# WBD_02.net
KiCad netlist of a schematic drawn in EAGLE
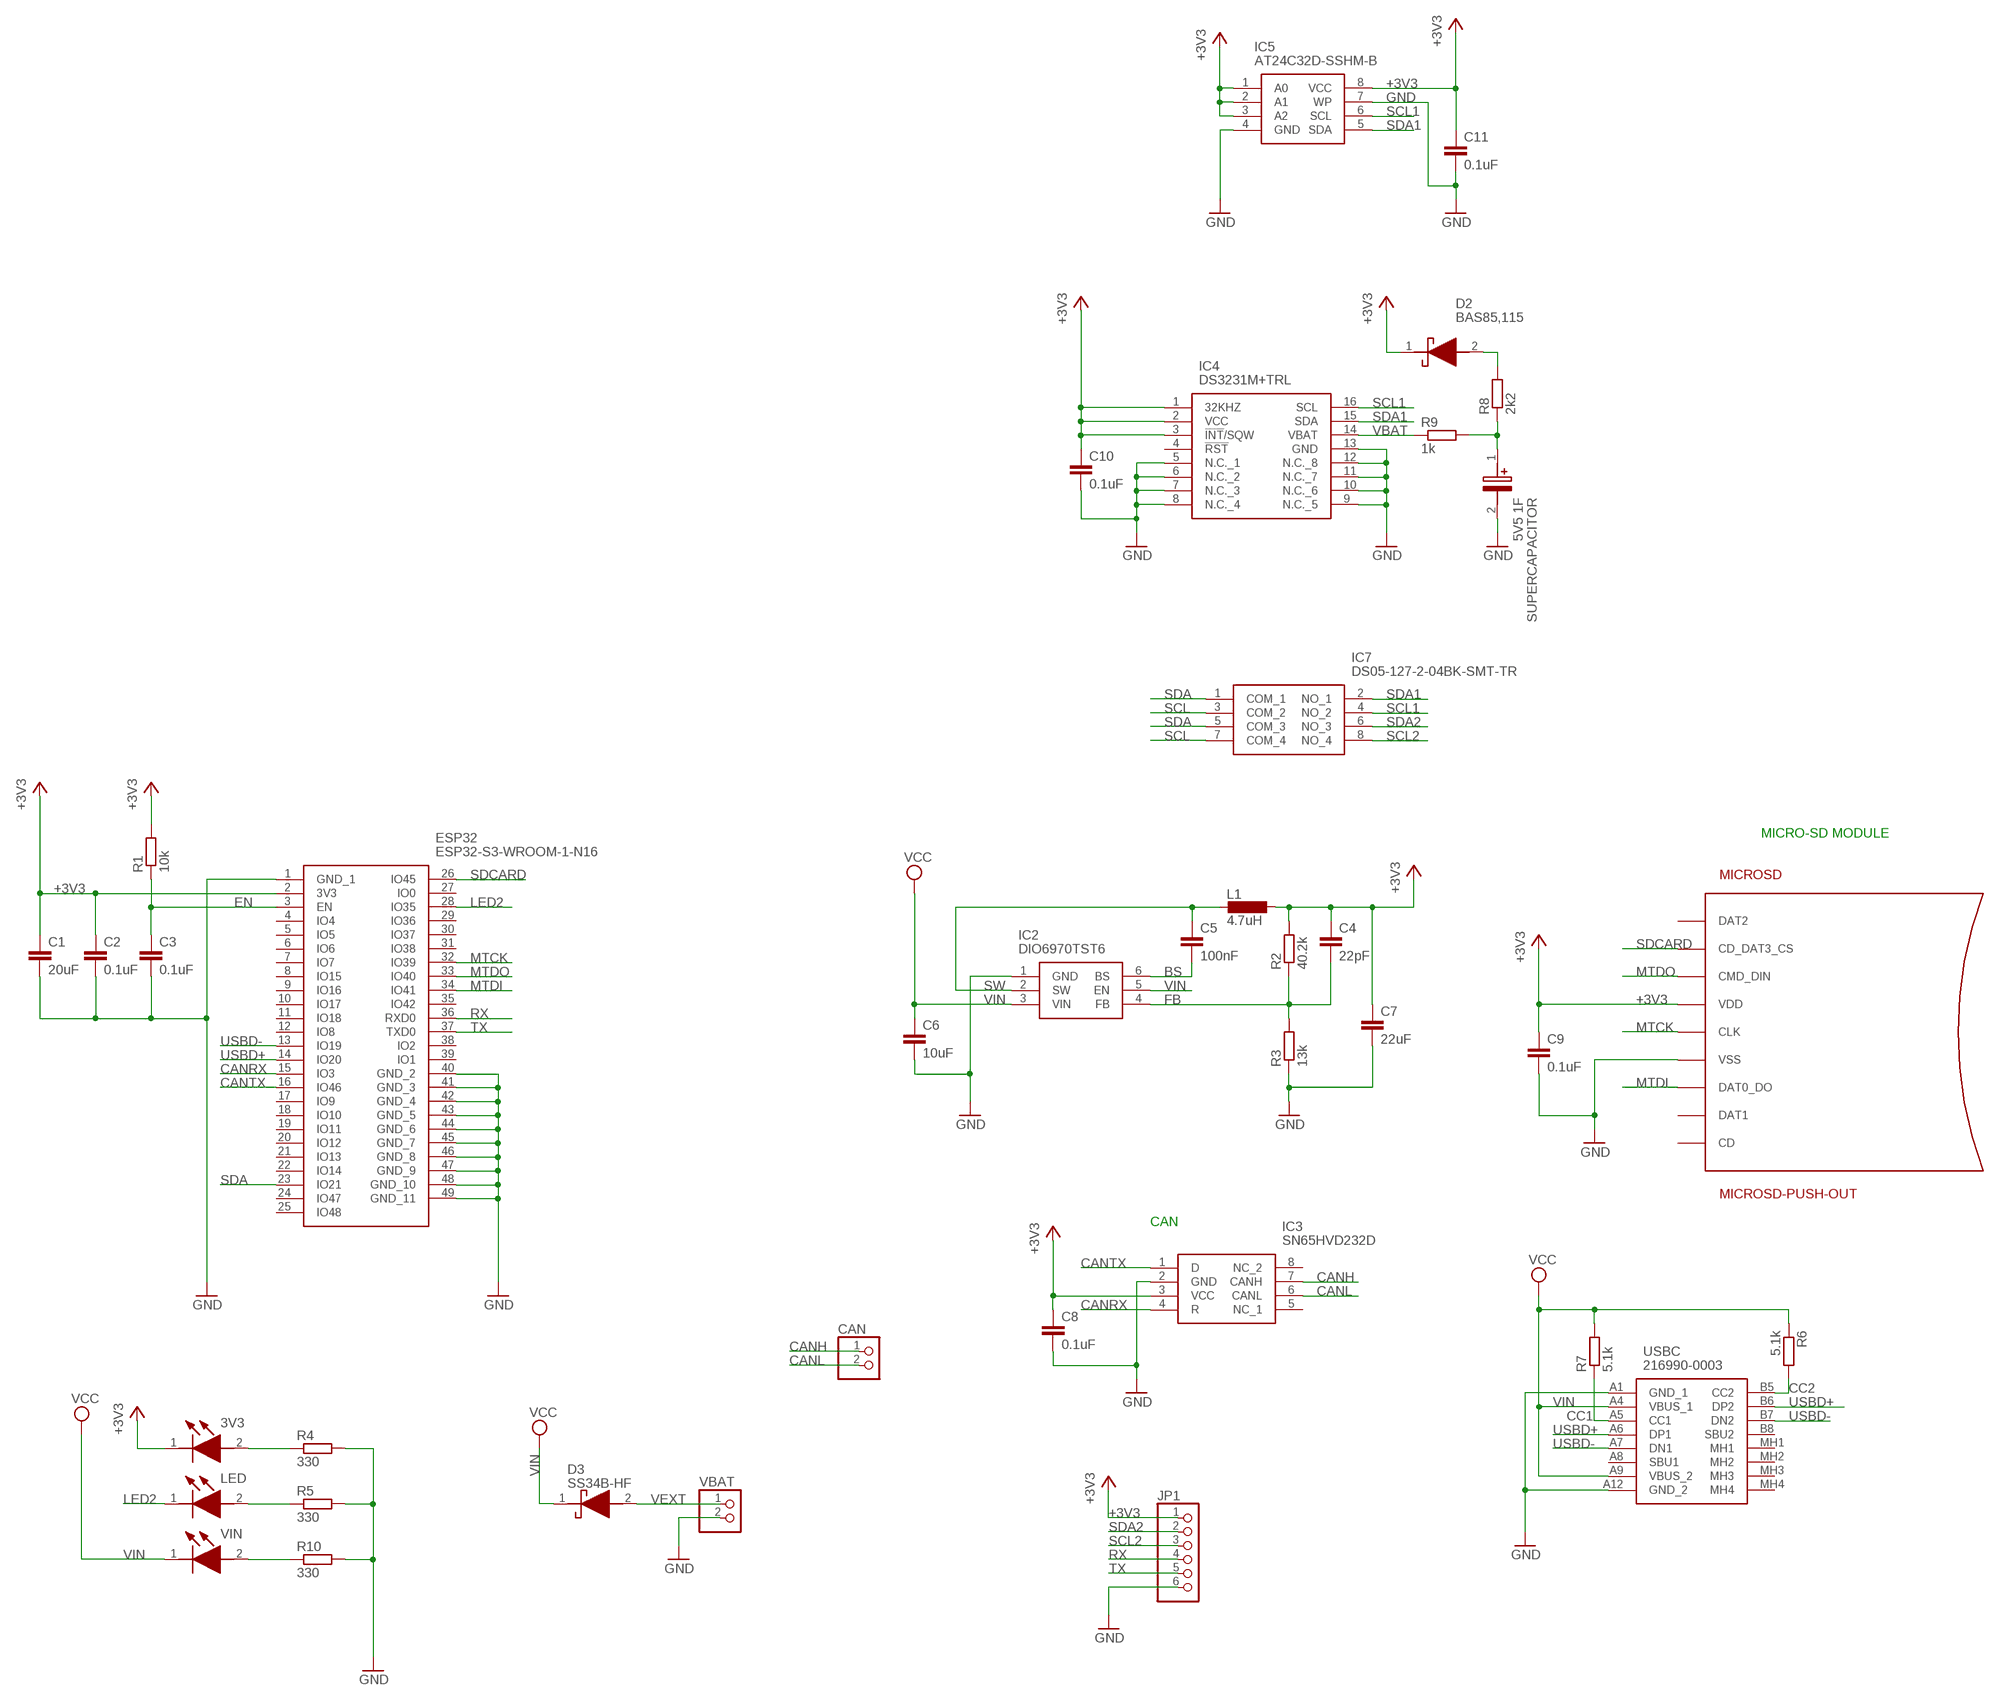
[diagram p0: schematic, sheet 1]

(export (version "E")
  (design (tool "Eeschema 10.0.6"))
  (components
    (comp (ref "3V3")
      (value "150060GS75000")
      (footprint "eagle-import:LEDC1608X80N")
      (fields (field (name "MOUSER_PART_NUMBER") "710-150060GS75000"))
      (libsource (lib "eagle-import") (part "150060GS75000"))
    )
    (comp (ref "C1")
      (value "20uF")
      (footprint "eagle-import:C0603")
      (libsource (lib "eagle-import") (part "C-EUC0603"))
    )
    (comp (ref "C2")
      (value "0.1uF")
      (footprint "eagle-import:C0603")
      (libsource (lib "eagle-import") (part "C-EUC0603"))
    )
    (comp (ref "C3")
      (value "0.1uF")
      (footprint "eagle-import:C0603")
      (libsource (lib "eagle-import") (part "C-EUC0603"))
    )
    (comp (ref "C4")
      (value "22pF")
      (footprint "eagle-import:C0603")
      (libsource (lib "eagle-import") (part "C-EUC0603"))
    )
    (comp (ref "C5")
      (value "100nF")
      (footprint "eagle-import:C0603")
      (libsource (lib "eagle-import") (part "C-EUC0603"))
    )
    (comp (ref "C6")
      (value "10uF")
      (footprint "eagle-import:C0603")
      (libsource (lib "eagle-import") (part "C-EUC0603"))
    )
    (comp (ref "C7")
      (value "22uF")
      (footprint "eagle-import:C0603")
      (libsource (lib "eagle-import") (part "C-EUC0603"))
    )
    (comp (ref "C8")
      (value "0.1uF")
      (footprint "eagle-import:C0603")
      (libsource (lib "eagle-import") (part "C-EUC0603"))
    )
    (comp (ref "C9")
      (value "0.1uF")
      (footprint "eagle-import:C0603")
      (libsource (lib "eagle-import") (part "C-EUC0603"))
    )
    (comp (ref "C10")
      (value "0.1uF")
      (footprint "eagle-import:C0603")
      (libsource (lib "eagle-import") (part "C-EUC0603"))
    )
    (comp (ref "C11")
      (value "0.1uF")
      (footprint "eagle-import:C0603")
      (libsource (lib "eagle-import") (part "C-EUC0603"))
    )
    (comp (ref "CAN")
      (value "PINHD-1X2")
      (footprint "eagle-import:1X02")
      (libsource (lib "eagle-import") (part "PINHD-1X2"))
    )
    (comp (ref "D2")
      (value "BAS85,115")
      (footprint "eagle-import:BAS85115")
      (fields (field (name "MOUSER_PART_NUMBER") "771-BAS85-T/R"))
      (libsource (lib "eagle-import") (part "BAS85,115"))
    )
    (comp (ref "D3")
      (value "SS34B-HF")
      (footprint "eagle-import:DIOM5336X320N")
      (fields (field (name "MOUSER_PART_NUMBER") "750-SS34B-HF"))
      (libsource (lib "eagle-import") (part "SS34B-HF"))
    )
    (comp (ref "ESP32")
      (value "ESP32-S3-WROOM-1-N16")
      (footprint "eagle-import:ESP32S3WROOM1N16")
      (fields (field (name "MOUSER_PART_NUMBER") "356-ESP32S3WROOM1N16"))
      (libsource (lib "eagle-import") (part "ESP32-S3-WROOM-1-N16"))
    )
    (comp (ref "IC2")
      (value "DIO6970TST6")
      (footprint "eagle-import:SOT95P280X90-6N")
      (fields (field (name "MOUSER_PART_NUMBER") "453-DIO6970ST6"))
      (libsource (lib "eagle-import") (part "DIO6970TST6"))
    )
    (comp (ref "IC3")
      (value "SN65HVD232D")
      (footprint "eagle-import:SOIC127P600X175-8N")
      (fields (field (name "MOUSER_PART_NUMBER") "595-SN65HVD232D"))
      (libsource (lib "eagle-import") (part "SN65HVD232D"))
    )
    (comp (ref "IC4")
      (value "DS3231M+TRL")
      (footprint "eagle-import:SOIC127P1032X265-16N")
      (fields (field (name "MOUSER_PART_NUMBER") "700-DS3231M+TRL"))
      (libsource (lib "eagle-import") (part "DS3231M+TRL"))
    )
    (comp (ref "IC5")
      (value "AT24C32D-SSHM-B")
      (footprint "eagle-import:SOIC127P600X175-8N")
      (fields (field (name "MOUSER_PART_NUMBER") "556-AT24C32D-SSHM-B"))
      (libsource (lib "eagle-import") (part "AT24C32D-SSHM-B"))
    )
    (comp (ref "IC7")
      (value "DS05-127-2-04BK-SMT-TR")
      (footprint "eagle-import:DS05127204BKSMTTR")
      (fields (field (name "MOUSER_PART_NUMBER") "490-DS05127204BK-STR"))
      (libsource (lib "eagle-import") (part "DS05-127-2-04BK-SMT-TR"))
    )
    (comp (ref "JP1")
      (value "PINHD-1X6")
      (footprint "eagle-import:1X06")
      (libsource (lib "eagle-import") (part "PINHD-1X6"))
    )
    (comp (ref "L1")
      (value "4.7uH")
      (footprint "eagle-import:L5650M")
      (libsource (lib "eagle-import") (part "L-EUL5650M"))
    )
    (comp (ref "LED")
      (value "150060GS75000")
      (footprint "eagle-import:LEDC1608X80N")
      (fields (field (name "MOUSER_PART_NUMBER") "710-150060GS75000"))
      (libsource (lib "eagle-import") (part "150060GS75000"))
    )
    (comp (ref "MICROSD")
      (value "MICROSD-PUSH-OUT")
      (footprint "eagle-import:MICROSD-PUSH-OUT")
      (libsource (lib "eagle-import") (part "MICROSD-PUSH-OUT"))
    )
    (comp (ref "R1")
      (value "10k")
      (footprint "eagle-import:R0603")
      (libsource (lib "eagle-import") (part "R-EU_R0603"))
    )
    (comp (ref "R2")
      (value "40.2k")
      (footprint "eagle-import:R0603")
      (libsource (lib "eagle-import") (part "R-EU_R0603"))
    )
    (comp (ref "R3")
      (value "13k")
      (footprint "eagle-import:R0603")
      (libsource (lib "eagle-import") (part "R-EU_R0603"))
    )
    (comp (ref "R4")
      (value "330")
      (footprint "eagle-import:R0603")
      (libsource (lib "eagle-import") (part "R-EU_R0603"))
    )
    (comp (ref "R5")
      (value "330")
      (footprint "eagle-import:R0603")
      (libsource (lib "eagle-import") (part "R-EU_R0603"))
    )
    (comp (ref "R6")
      (value "5.1k")
      (footprint "eagle-import:R0603")
      (libsource (lib "eagle-import") (part "R-EU_R0603"))
    )
    (comp (ref "R7")
      (value "5.1k")
      (footprint "eagle-import:R0603")
      (libsource (lib "eagle-import") (part "R-EU_R0603"))
    )
    (comp (ref "R8")
      (value "2k2")
      (footprint "eagle-import:R0603")
      (libsource (lib "eagle-import") (part "R-EU_R0603"))
    )
    (comp (ref "R9")
      (value "1k")
      (footprint "eagle-import:R0603")
      (libsource (lib "eagle-import") (part "R-EU_R0603"))
    )
    (comp (ref "R10")
      (value "330")
      (footprint "eagle-import:R0603")
      (libsource (lib "eagle-import") (part "R-EU_R0603"))
    )
    (comp (ref "SUPERCAPACITOR")
      (value "5V5 1F")
      (footprint "eagle-import:CAPPRD500W130D2150H800")
      (fields
        (field (name "MANUFACTURER_PART_NUMBER") "DB-5R5D105T")
        (field (name "MOUSER_PART_NUMBER") "555-DB-5R5D105T")
      )
      (libsource (lib "eagle-import") (part "DB-5R5D105T"))
    )
    (comp (ref "USBC")
      (value "216990-0003")
      (footprint "eagle-import:2169900003")
      (fields (field (name "MOUSER_PART_NUMBER") "538-216990-0003"))
      (libsource (lib "eagle-import") (part "216990-0003"))
    )
    (comp (ref "VBAT")
      (value "PINHD-1X2")
      (footprint "eagle-import:1X02")
      (libsource (lib "eagle-import") (part "PINHD-1X2"))
    )
    (comp (ref "VIN")
      (value "150060GS75000")
      (footprint "eagle-import:LEDC1608X80N")
      (fields (field (name "MOUSER_PART_NUMBER") "710-150060GS75000"))
      (libsource (lib "eagle-import") (part "150060GS75000"))
    )
  )
  (nets
    (net (code "1") (name "+3V3") (class "Default")
      (node (ref "3V3") (pin "1") (pinfunction "K_1") (pintype "bidirectional"))
      (node (ref "C1") (pin "1") (pinfunction "1_1") (pintype "passive"))
      (node (ref "C10") (pin "1") (pinfunction "1_1") (pintype "passive"))
      (node (ref "C11") (pin "1") (pinfunction "1_1") (pintype "passive"))
      (node (ref "C2") (pin "1") (pinfunction "1_1") (pintype "passive"))
      (node (ref "C4") (pin "1") (pinfunction "1_1") (pintype "passive"))
      (node (ref "C7") (pin "1") (pinfunction "1_1") (pintype "passive"))
      (node (ref "C8") (pin "1") (pinfunction "1_1") (pintype "passive"))
      (node (ref "C9") (pin "1") (pinfunction "1_1") (pintype "passive"))
      (node (ref "D2") (pin "1") (pinfunction "K_1") (pintype "bidirectional"))
      (node (ref "ESP32") (pin "2") (pinfunction "3V3_2") (pintype "bidirectional"))
      (node (ref "IC3") (pin "3") (pinfunction "VCC_3") (pintype "bidirectional"))
      (node (ref "IC4") (pin "1") (pinfunction "32KHZ_1") (pintype "bidirectional"))
      (node (ref "IC4") (pin "2") (pinfunction "VCC_2") (pintype "bidirectional"))
      (node (ref "IC4") (pin "3") (pinfunction "~{INT}/SQW_3") (pintype "bidirectional"))
      (node (ref "IC5") (pin "1") (pinfunction "A0_1") (pintype "bidirectional"))
      (node (ref "IC5") (pin "2") (pinfunction "A1_2") (pintype "bidirectional"))
      (node (ref "IC5") (pin "3") (pinfunction "A2_3") (pintype "bidirectional"))
      (node (ref "IC5") (pin "8") (pinfunction "VCC_8") (pintype "bidirectional"))
      (node (ref "JP1") (pin "1") (pinfunction "1_1") (pintype "passive"))
      (node (ref "L1") (pin "1") (pinfunction "1_1") (pintype "passive"))
      (node (ref "MICROSD") (pin "4") (pinfunction "VDD_4") (pintype "bidirectional"))
      (node (ref "R1") (pin "2") (pinfunction "2_2") (pintype "passive"))
      (node (ref "R2") (pin "2") (pinfunction "2_2") (pintype "passive"))
    )
    (net (code "2") (name "/BS") (class "Default")
      (node (ref "C5") (pin "2") (pinfunction "2_2") (pintype "passive"))
      (node (ref "IC2") (pin "6") (pinfunction "BS_6") (pintype "bidirectional"))
    )
    (net (code "3") (name "/CANH") (class "Default")
      (node (ref "CAN") (pin "1") (pinfunction "1_1") (pintype "passive"))
      (node (ref "IC3") (pin "7") (pinfunction "CANH_7") (pintype "bidirectional"))
    )
    (net (code "4") (name "/CANL") (class "Default")
      (node (ref "CAN") (pin "2") (pinfunction "2_2") (pintype "passive"))
      (node (ref "IC3") (pin "6") (pinfunction "CANL_6") (pintype "bidirectional"))
    )
    (net (code "5") (name "/CANRX") (class "Default")
      (node (ref "ESP32") (pin "15") (pinfunction "IO3_15") (pintype "bidirectional"))
      (node (ref "IC3") (pin "4") (pinfunction "R_4") (pintype "bidirectional"))
    )
    (net (code "6") (name "/CANTX") (class "Default")
      (node (ref "ESP32") (pin "16") (pinfunction "IO46_16") (pintype "bidirectional"))
      (node (ref "IC3") (pin "1") (pinfunction "D_1") (pintype "bidirectional"))
    )
    (net (code "7") (name "/CC1") (class "Default")
      (node (ref "R7") (pin "1") (pinfunction "1_1") (pintype "passive"))
      (node (ref "USBC") (pin "A5") (pinfunction "CC1_A5") (pintype "bidirectional"))
    )
    (net (code "8") (name "/CC2") (class "Default")
      (node (ref "R6") (pin "2") (pinfunction "2_2") (pintype "passive"))
      (node (ref "USBC") (pin "B5") (pinfunction "CC2_B5") (pintype "bidirectional"))
    )
    (net (code "9") (name "/EN") (class "Default")
      (node (ref "C3") (pin "1") (pinfunction "1_1") (pintype "passive"))
      (node (ref "ESP32") (pin "3") (pinfunction "EN_3") (pintype "bidirectional"))
      (node (ref "R1") (pin "1") (pinfunction "1_1") (pintype "passive"))
    )
    (net (code "10") (name "/FB") (class "Default")
      (node (ref "C4") (pin "2") (pinfunction "2_2") (pintype "passive"))
      (node (ref "IC2") (pin "4") (pinfunction "FB_4") (pintype "bidirectional"))
      (node (ref "R2") (pin "1") (pinfunction "1_1") (pintype "passive"))
      (node (ref "R3") (pin "2") (pinfunction "2_2") (pintype "passive"))
    )
    (net (code "11") (name "/LED2") (class "Default")
      (node (ref "ESP32") (pin "28") (pinfunction "IO35_28") (pintype "bidirectional"))
      (node (ref "LED") (pin "1") (pinfunction "K_1") (pintype "bidirectional"))
    )
    (net (code "12") (name "/MTCK") (class "Default")
      (node (ref "ESP32") (pin "32") (pinfunction "IO39_32") (pintype "bidirectional"))
      (node (ref "MICROSD") (pin "5") (pinfunction "CLK_5") (pintype "bidirectional"))
    )
    (net (code "13") (name "/MTDI") (class "Default")
      (node (ref "ESP32") (pin "34") (pinfunction "IO41_34") (pintype "bidirectional"))
      (node (ref "MICROSD") (pin "7") (pinfunction "DAT0_DO_7") (pintype "bidirectional"))
    )
    (net (code "14") (name "/MTDO") (class "Default")
      (node (ref "ESP32") (pin "33") (pinfunction "IO40_33") (pintype "bidirectional"))
      (node (ref "MICROSD") (pin "3") (pinfunction "CMD_DIN_3") (pintype "bidirectional"))
    )
    (net (code "15") (name "/RX") (class "Default")
      (node (ref "ESP32") (pin "36") (pinfunction "RXD0_36") (pintype "bidirectional"))
      (node (ref "JP1") (pin "4") (pinfunction "4_4") (pintype "passive"))
    )
    (net (code "16") (name "/SCL") (class "Default")
      (node (ref "IC7") (pin "3") (pinfunction "COM_2_3") (pintype "bidirectional"))
      (node (ref "IC7") (pin "7") (pinfunction "COM_4_7") (pintype "bidirectional"))
    )
    (net (code "17") (name "/SCL1") (class "Default")
      (node (ref "IC4") (pin "16") (pinfunction "SCL_16") (pintype "bidirectional"))
      (node (ref "IC5") (pin "6") (pinfunction "SCL_6") (pintype "bidirectional"))
      (node (ref "IC7") (pin "4") (pinfunction "NO_2_4") (pintype "bidirectional"))
    )
    (net (code "18") (name "/SCL2") (class "Default")
      (node (ref "IC7") (pin "8") (pinfunction "NO_4_8") (pintype "bidirectional"))
      (node (ref "JP1") (pin "3") (pinfunction "3_3") (pintype "passive"))
    )
    (net (code "19") (name "/SDA") (class "Default")
      (node (ref "ESP32") (pin "23") (pinfunction "IO21_23") (pintype "bidirectional"))
      (node (ref "IC7") (pin "1") (pinfunction "COM_1_1") (pintype "bidirectional"))
      (node (ref "IC7") (pin "5") (pinfunction "COM_3_5") (pintype "bidirectional"))
    )
    (net (code "20") (name "/SDA1") (class "Default")
      (node (ref "IC4") (pin "15") (pinfunction "SDA_15") (pintype "bidirectional"))
      (node (ref "IC5") (pin "5") (pinfunction "SDA_5") (pintype "bidirectional"))
      (node (ref "IC7") (pin "2") (pinfunction "NO_1_2") (pintype "bidirectional"))
    )
    (net (code "21") (name "/SDA2") (class "Default")
      (node (ref "IC7") (pin "6") (pinfunction "NO_3_6") (pintype "bidirectional"))
      (node (ref "JP1") (pin "2") (pinfunction "2_2") (pintype "passive"))
    )
    (net (code "22") (name "/SDCARD") (class "Default")
      (node (ref "ESP32") (pin "26") (pinfunction "IO45_26") (pintype "bidirectional"))
      (node (ref "MICROSD") (pin "2") (pinfunction "CD_DAT3_CS_2") (pintype "bidirectional"))
    )
    (net (code "23") (name "/SW") (class "Default")
      (node (ref "C5") (pin "1") (pinfunction "1_1") (pintype "passive"))
      (node (ref "IC2") (pin "2") (pinfunction "SW_2") (pintype "bidirectional"))
      (node (ref "L1") (pin "2") (pinfunction "2_2") (pintype "passive"))
    )
    (net (code "24") (name "/TX") (class "Default")
      (node (ref "ESP32") (pin "37") (pinfunction "TXD0_37") (pintype "bidirectional"))
      (node (ref "JP1") (pin "5") (pinfunction "5_5") (pintype "passive"))
    )
    (net (code "25") (name "/USBD+") (class "Default")
      (node (ref "ESP32") (pin "14") (pinfunction "IO20_14") (pintype "bidirectional"))
      (node (ref "USBC") (pin "A6") (pinfunction "DP1_A6") (pintype "bidirectional"))
      (node (ref "USBC") (pin "B6") (pinfunction "DP2_B6") (pintype "bidirectional"))
    )
    (net (code "26") (name "/USBD-") (class "Default")
      (node (ref "ESP32") (pin "13") (pinfunction "IO19_13") (pintype "bidirectional"))
      (node (ref "USBC") (pin "A7") (pinfunction "DN1_A7") (pintype "bidirectional"))
      (node (ref "USBC") (pin "B7") (pinfunction "DN2_B7") (pintype "bidirectional"))
    )
    (net (code "27") (name "/VBAT") (class "Default")
      (node (ref "IC4") (pin "14") (pinfunction "VBAT_14") (pintype "bidirectional"))
      (node (ref "R9") (pin "1") (pinfunction "1_1") (pintype "passive"))
    )
    (net (code "28") (name "/VEXT") (class "Default")
      (node (ref "D3") (pin "2") (pinfunction "A_2") (pintype "bidirectional"))
      (node (ref "VBAT") (pin "1") (pinfunction "1_1") (pintype "passive"))
    )
    (net (code "29") (name "GND") (class "Default")
      (node (ref "C1") (pin "2") (pinfunction "2_2") (pintype "passive"))
      (node (ref "C10") (pin "2") (pinfunction "2_2") (pintype "passive"))
      (node (ref "C11") (pin "2") (pinfunction "2_2") (pintype "passive"))
      (node (ref "C2") (pin "2") (pinfunction "2_2") (pintype "passive"))
      (node (ref "C3") (pin "2") (pinfunction "2_2") (pintype "passive"))
      (node (ref "C6") (pin "2") (pinfunction "2_2") (pintype "passive"))
      (node (ref "C7") (pin "2") (pinfunction "2_2") (pintype "passive"))
      (node (ref "C8") (pin "2") (pinfunction "2_2") (pintype "passive"))
      (node (ref "C9") (pin "2") (pinfunction "2_2") (pintype "passive"))
      (node (ref "ESP32") (pin "1") (pinfunction "GND_1_1") (pintype "bidirectional"))
      (node (ref "ESP32") (pin "40") (pinfunction "GND_2_40") (pintype "bidirectional"))
      (node (ref "ESP32") (pin "41") (pinfunction "GND_3_41") (pintype "bidirectional"))
      (node (ref "ESP32") (pin "42") (pinfunction "GND_4_42") (pintype "bidirectional"))
      (node (ref "ESP32") (pin "43") (pinfunction "GND_5_43") (pintype "bidirectional"))
      (node (ref "ESP32") (pin "44") (pinfunction "GND_6_44") (pintype "bidirectional"))
      (node (ref "ESP32") (pin "45") (pinfunction "GND_7_45") (pintype "bidirectional"))
      (node (ref "ESP32") (pin "46") (pinfunction "GND_8_46") (pintype "bidirectional"))
      (node (ref "ESP32") (pin "47") (pinfunction "GND_9_47") (pintype "bidirectional"))
      (node (ref "ESP32") (pin "48") (pinfunction "GND_10_48") (pintype "bidirectional"))
      (node (ref "ESP32") (pin "49") (pinfunction "GND_11_49") (pintype "bidirectional"))
      (node (ref "IC2") (pin "1") (pinfunction "GND_1") (pintype "bidirectional"))
      (node (ref "IC3") (pin "2") (pinfunction "GND_2") (pintype "bidirectional"))
      (node (ref "IC4") (pin "10") (pinfunction "N.C._6_10") (pintype "bidirectional"))
      (node (ref "IC4") (pin "11") (pinfunction "N.C._7_11") (pintype "bidirectional"))
      (node (ref "IC4") (pin "12") (pinfunction "N.C._8_12") (pintype "bidirectional"))
      (node (ref "IC4") (pin "13") (pinfunction "GND_13") (pintype "bidirectional"))
      (node (ref "IC4") (pin "5") (pinfunction "N.C._1_5") (pintype "bidirectional"))
      (node (ref "IC4") (pin "6") (pinfunction "N.C._2_6") (pintype "bidirectional"))
      (node (ref "IC4") (pin "7") (pinfunction "N.C._3_7") (pintype "bidirectional"))
      (node (ref "IC4") (pin "8") (pinfunction "N.C._4_8") (pintype "bidirectional"))
      (node (ref "IC4") (pin "9") (pinfunction "N.C._5_9") (pintype "bidirectional"))
      (node (ref "IC5") (pin "4") (pinfunction "GND_4") (pintype "bidirectional"))
      (node (ref "IC5") (pin "7") (pinfunction "WP_7") (pintype "bidirectional"))
      (node (ref "JP1") (pin "6") (pinfunction "6_6") (pintype "passive"))
      (node (ref "MICROSD") (pin "6") (pinfunction "VSS_6") (pintype "bidirectional"))
      (node (ref "MICROSD") (pin "G1") (pinfunction "VSS_G1") (pintype "bidirectional"))
      (node (ref "MICROSD") (pin "G2") (pinfunction "VSS_G2") (pintype "bidirectional"))
      (node (ref "MICROSD") (pin "G3") (pinfunction "VSS_G3") (pintype "bidirectional"))
      (node (ref "MICROSD") (pin "G4") (pinfunction "VSS_G4") (pintype "bidirectional"))
      (node (ref "R10") (pin "2") (pinfunction "2_2") (pintype "passive"))
      (node (ref "R3") (pin "1") (pinfunction "1_1") (pintype "passive"))
      (node (ref "R4") (pin "2") (pinfunction "2_2") (pintype "passive"))
      (node (ref "R5") (pin "2") (pinfunction "2_2") (pintype "passive"))
      (node (ref "SUPERCAPACITOR") (pin "2") (pinfunction "-_2") (pintype "bidirectional"))
      (node (ref "USBC") (pin "A1") (pinfunction "GND_1_A1") (pintype "bidirectional"))
      (node (ref "USBC") (pin "A12") (pinfunction "GND_2_A12") (pintype "bidirectional"))
      (node (ref "VBAT") (pin "2") (pinfunction "2_2") (pintype "passive"))
    )
    (net (code "30") (name "Net-(3V3-A)") (class "Default")
      (node (ref "3V3") (pin "2") (pinfunction "A_2") (pintype "bidirectional"))
      (node (ref "R4") (pin "1") (pinfunction "1_1") (pintype "passive"))
    )
    (net (code "31") (name "Net-(D2-A)") (class "Default")
      (node (ref "D2") (pin "2") (pinfunction "A_2") (pintype "bidirectional"))
      (node (ref "R8") (pin "2") (pinfunction "2_2") (pintype "passive"))
    )
    (net (code "32") (name "Net-(LED-A)") (class "Default")
      (node (ref "LED") (pin "2") (pinfunction "A_2") (pintype "bidirectional"))
      (node (ref "R5") (pin "1") (pinfunction "1_1") (pintype "passive"))
    )
    (net (code "33") (name "Net-(SUPERCAPACITOR-+)") (class "Default")
      (node (ref "R8") (pin "1") (pinfunction "1_1") (pintype "passive"))
      (node (ref "R9") (pin "2") (pinfunction "2_2") (pintype "passive"))
      (node (ref "SUPERCAPACITOR") (pin "1") (pinfunction "+_1") (pintype "bidirectional"))
    )
    (net (code "34") (name "Net-(VIN-A)") (class "Default")
      (node (ref "R10") (pin "1") (pinfunction "1_1") (pintype "passive"))
      (node (ref "VIN") (pin "2") (pinfunction "A_2") (pintype "bidirectional"))
    )
    (net (code "35") (name "VCC") (class "Default")
      (node (ref "C6") (pin "1") (pinfunction "1_1") (pintype "passive"))
      (node (ref "D3") (pin "1") (pinfunction "K_1") (pintype "bidirectional"))
      (node (ref "IC2") (pin "3") (pinfunction "VIN_3") (pintype "bidirectional"))
      (node (ref "IC2") (pin "5") (pinfunction "EN_5") (pintype "bidirectional"))
      (node (ref "R6") (pin "1") (pinfunction "1_1") (pintype "passive"))
      (node (ref "R7") (pin "2") (pinfunction "2_2") (pintype "passive"))
      (node (ref "USBC") (pin "A4") (pinfunction "VBUS_1_A4") (pintype "bidirectional"))
      (node (ref "USBC") (pin "A9") (pinfunction "VBUS_2_A9") (pintype "bidirectional"))
      (node (ref "VIN") (pin "1") (pinfunction "K_1") (pintype "bidirectional"))
    )
    (net (code "36") (name "unconnected-(ESP32-IO0-Pad27)") (class "Default")
      (node (ref "ESP32") (pin "27") (pinfunction "IO0_27") (pintype "bidirectional"))
    )
    (net (code "37") (name "unconnected-(ESP32-IO1-Pad39)") (class "Default")
      (node (ref "ESP32") (pin "39") (pinfunction "IO1_39") (pintype "bidirectional"))
    )
    (net (code "38") (name "unconnected-(ESP32-IO2-Pad38)") (class "Default")
      (node (ref "ESP32") (pin "38") (pinfunction "IO2_38") (pintype "bidirectional"))
    )
    (net (code "39") (name "unconnected-(ESP32-IO4-Pad4)") (class "Default")
      (node (ref "ESP32") (pin "4") (pinfunction "IO4_4") (pintype "bidirectional"))
    )
    (net (code "40") (name "unconnected-(ESP32-IO5-Pad5)") (class "Default")
      (node (ref "ESP32") (pin "5") (pinfunction "IO5_5") (pintype "bidirectional"))
    )
    (net (code "41") (name "unconnected-(ESP32-IO6-Pad6)") (class "Default")
      (node (ref "ESP32") (pin "6") (pinfunction "IO6_6") (pintype "bidirectional"))
    )
    (net (code "42") (name "unconnected-(ESP32-IO7-Pad7)") (class "Default")
      (node (ref "ESP32") (pin "7") (pinfunction "IO7_7") (pintype "bidirectional"))
    )
    (net (code "43") (name "unconnected-(ESP32-IO8-Pad12)") (class "Default")
      (node (ref "ESP32") (pin "12") (pinfunction "IO8_12") (pintype "bidirectional"))
    )
    (net (code "44") (name "unconnected-(ESP32-IO9-Pad17)") (class "Default")
      (node (ref "ESP32") (pin "17") (pinfunction "IO9_17") (pintype "bidirectional"))
    )
    (net (code "45") (name "unconnected-(ESP32-IO10-Pad18)") (class "Default")
      (node (ref "ESP32") (pin "18") (pinfunction "IO10_18") (pintype "bidirectional"))
    )
    (net (code "46") (name "unconnected-(ESP32-IO11-Pad19)") (class "Default")
      (node (ref "ESP32") (pin "19") (pinfunction "IO11_19") (pintype "bidirectional"))
    )
    (net (code "47") (name "unconnected-(ESP32-IO12-Pad20)") (class "Default")
      (node (ref "ESP32") (pin "20") (pinfunction "IO12_20") (pintype "bidirectional"))
    )
    (net (code "48") (name "unconnected-(ESP32-IO13-Pad21)") (class "Default")
      (node (ref "ESP32") (pin "21") (pinfunction "IO13_21") (pintype "bidirectional"))
    )
    (net (code "49") (name "unconnected-(ESP32-IO14-Pad22)") (class "Default")
      (node (ref "ESP32") (pin "22") (pinfunction "IO14_22") (pintype "bidirectional"))
    )
    (net (code "50") (name "unconnected-(ESP32-IO15-Pad8)") (class "Default")
      (node (ref "ESP32") (pin "8") (pinfunction "IO15_8") (pintype "bidirectional"))
    )
    (net (code "51") (name "unconnected-(ESP32-IO16-Pad9)") (class "Default")
      (node (ref "ESP32") (pin "9") (pinfunction "IO16_9") (pintype "bidirectional"))
    )
    (net (code "52") (name "unconnected-(ESP32-IO17-Pad10)") (class "Default")
      (node (ref "ESP32") (pin "10") (pinfunction "IO17_10") (pintype "bidirectional"))
    )
    (net (code "53") (name "unconnected-(ESP32-IO18-Pad11)") (class "Default")
      (node (ref "ESP32") (pin "11") (pinfunction "IO18_11") (pintype "bidirectional"))
    )
    (net (code "54") (name "unconnected-(ESP32-IO36-Pad29)") (class "Default")
      (node (ref "ESP32") (pin "29") (pinfunction "IO36_29") (pintype "bidirectional"))
    )
    (net (code "55") (name "unconnected-(ESP32-IO37-Pad30)") (class "Default")
      (node (ref "ESP32") (pin "30") (pinfunction "IO37_30") (pintype "bidirectional"))
    )
    (net (code "56") (name "unconnected-(ESP32-IO38-Pad31)") (class "Default")
      (node (ref "ESP32") (pin "31") (pinfunction "IO38_31") (pintype "bidirectional"))
    )
    (net (code "57") (name "unconnected-(ESP32-IO42-Pad35)") (class "Default")
      (node (ref "ESP32") (pin "35") (pinfunction "IO42_35") (pintype "bidirectional"))
    )
    (net (code "58") (name "unconnected-(ESP32-IO47-Pad24)") (class "Default")
      (node (ref "ESP32") (pin "24") (pinfunction "IO47_24") (pintype "bidirectional"))
    )
    (net (code "59") (name "unconnected-(ESP32-IO48-Pad25)") (class "Default")
      (node (ref "ESP32") (pin "25") (pinfunction "IO48_25") (pintype "bidirectional"))
    )
    (net (code "60") (name "unconnected-(IC3-NC_1-Pad5)") (class "Default")
      (node (ref "IC3") (pin "5") (pinfunction "NC_1_5") (pintype "bidirectional"))
    )
    (net (code "61") (name "unconnected-(IC3-NC_2-Pad8)") (class "Default")
      (node (ref "IC3") (pin "8") (pinfunction "NC_2_8") (pintype "bidirectional"))
    )
    (net (code "62") (name "unconnected-(IC4-~{RST}-Pad4)") (class "Default")
      (node (ref "IC4") (pin "4") (pinfunction "~{RST}_4") (pintype "bidirectional"))
    )
    (net (code "63") (name "unconnected-(MICROSD-DAT1-Pad8)") (class "Default")
      (node (ref "MICROSD") (pin "8") (pinfunction "DAT1_8") (pintype "bidirectional"))
    )
    (net (code "64") (name "unconnected-(MICROSD-DAT2-Pad1)") (class "Default")
      (node (ref "MICROSD") (pin "1") (pinfunction "DAT2_1") (pintype "bidirectional"))
    )
    (net (code "65") (name "unconnected-(MICROSD-PadCD)") (class "Default")
      (node (ref "MICROSD") (pin "CD") (pinfunction "CD_CD") (pintype "bidirectional"))
    )
    (net (code "66") (name "unconnected-(USBC-PadMH1)") (class "Default")
      (node (ref "USBC") (pin "MH1") (pinfunction "MH1_MH1") (pintype "bidirectional"))
    )
    (net (code "67") (name "unconnected-(USBC-PadMH2)") (class "Default")
      (node (ref "USBC") (pin "MH2") (pinfunction "MH2_MH2") (pintype "bidirectional"))
    )
    (net (code "68") (name "unconnected-(USBC-PadMH3)") (class "Default")
      (node (ref "USBC") (pin "MH3") (pinfunction "MH3_MH3") (pintype "bidirectional"))
    )
    (net (code "69") (name "unconnected-(USBC-PadMH4)") (class "Default")
      (node (ref "USBC") (pin "MH4") (pinfunction "MH4_MH4") (pintype "bidirectional"))
    )
    (net (code "70") (name "unconnected-(USBC-SBU1-PadA8)") (class "Default")
      (node (ref "USBC") (pin "A8") (pinfunction "SBU1_A8") (pintype "bidirectional"))
    )
    (net (code "71") (name "unconnected-(USBC-SBU2-PadB8)") (class "Default")
      (node (ref "USBC") (pin "B8") (pinfunction "SBU2_B8") (pintype "bidirectional"))
    )
  )
)
